# bus.net
KiCad netlist of a schematic drawn in Altium Designer
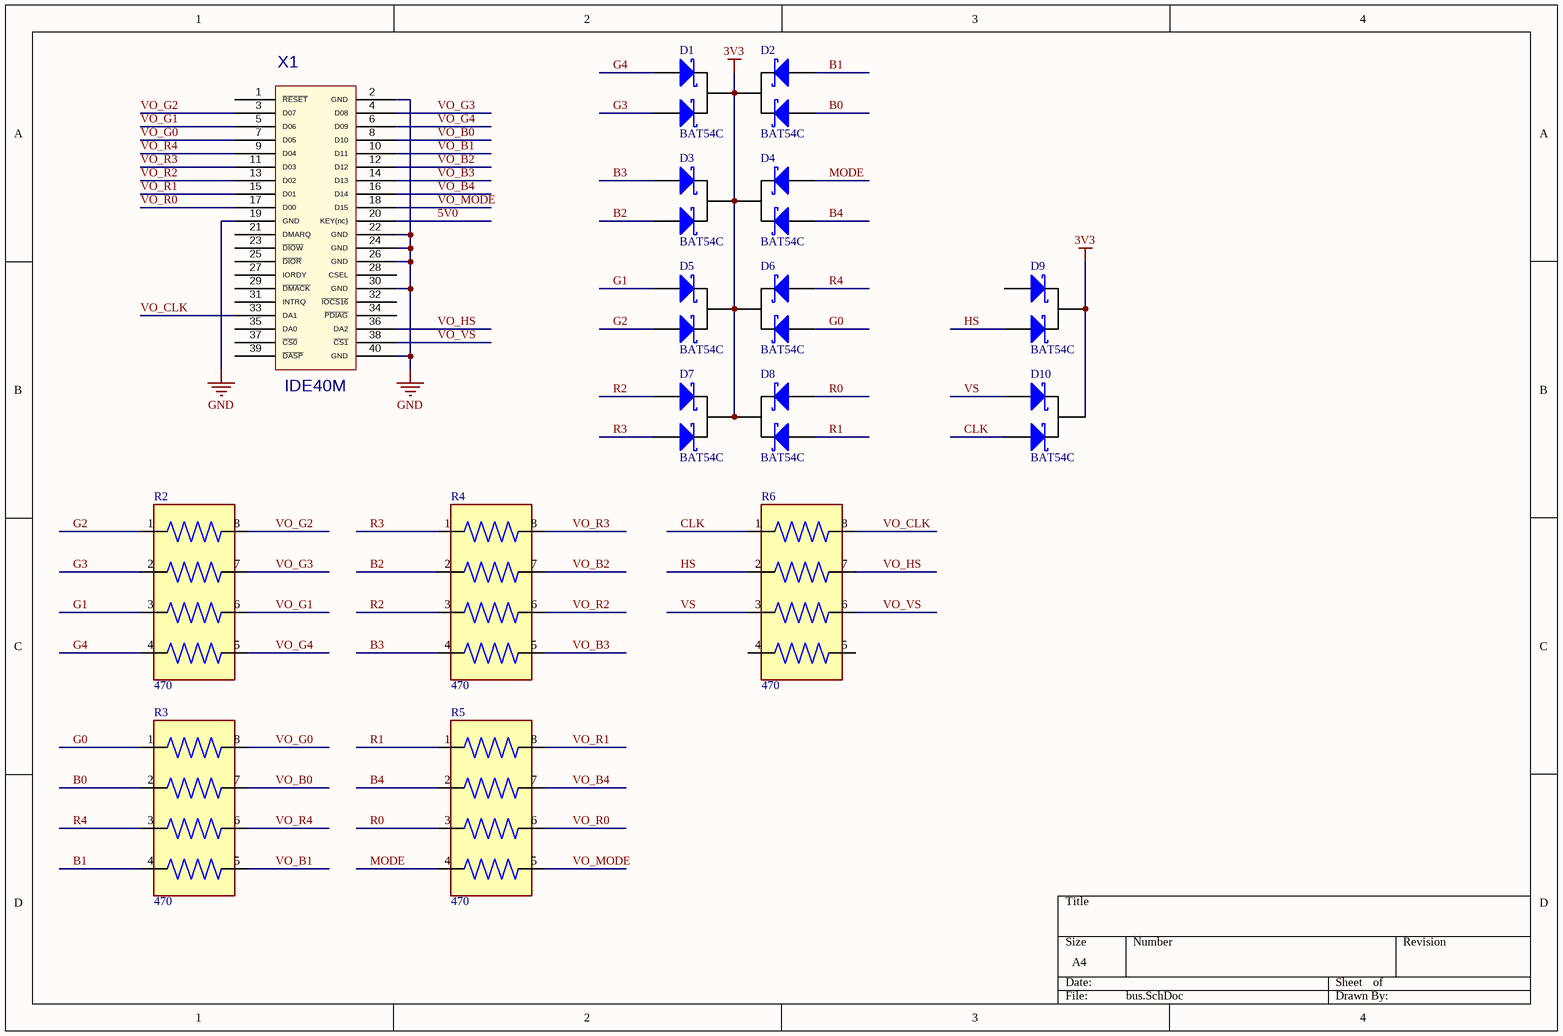
[diagram p0: bus.SchDoc]

(export (version "E")
  (design (tool "Eeschema 10.0.6"))
  (components
    (comp (ref "D1") (value "BAT54C") (footprint "SOT-23") (libsource (lib "Schlib") (part "BAT54C")))
    (comp (ref "D2") (value "BAT54C") (footprint "SOT-23") (libsource (lib "Schlib") (part "BAT54C")))
    (comp (ref "D3") (value "BAT54C") (footprint "SOT-23") (libsource (lib "Schlib") (part "BAT54C")))
    (comp (ref "D4") (value "BAT54C") (footprint "SOT-23") (libsource (lib "Schlib") (part "BAT54C")))
    (comp (ref "D5") (value "BAT54C") (footprint "SOT-23") (libsource (lib "Schlib") (part "BAT54C")))
    (comp (ref "D6") (value "BAT54C") (footprint "SOT-23") (libsource (lib "Schlib") (part "BAT54C")))
    (comp (ref "D7") (value "BAT54C") (footprint "SOT-23") (libsource (lib "Schlib") (part "BAT54C")))
    (comp (ref "D8") (value "BAT54C") (footprint "SOT-23") (libsource (lib "Schlib") (part "BAT54C")))
    (comp (ref "D9") (value "BAT54C") (footprint "SOT-23") (libsource (lib "Schlib") (part "BAT54C")))
    (comp (ref "D10") (value "BAT54C") (footprint "SOT-23") (libsource (lib "Schlib") (part "BAT54C")))
    (comp (ref "R2")
      (value "470")
      (footprint "RESCAV50P200X100X55-8N")
      (fields (field (name "MP") "CAT10-101J4LF"))
      (libsource (lib "Schlib") (part "CAT10-***4LF"))
    )
    (comp (ref "R3")
      (value "470")
      (footprint "RESCAV50P200X100X55-8N")
      (fields (field (name "MP") "CAT10-101J4LF"))
      (libsource (lib "Schlib") (part "CAT10-***4LF"))
    )
    (comp (ref "R4")
      (value "470")
      (footprint "RESCAV50P200X100X55-8N")
      (fields (field (name "MP") "CAT10-101J4LF"))
      (libsource (lib "Schlib") (part "CAT10-***4LF"))
    )
    (comp (ref "R5")
      (value "470")
      (footprint "RESCAV50P200X100X55-8N")
      (fields (field (name "MP") "CAT10-101J4LF"))
      (libsource (lib "Schlib") (part "CAT10-***4LF"))
    )
    (comp (ref "R6")
      (value "470")
      (footprint "RESCAV50P200X100X55-8N")
      (fields (field (name "MP") "CAT10-101J4LF"))
      (libsource (lib "Schlib") (part "CAT10-***4LF"))
    )
    (comp (ref "X1") (value "IDE40M") (footprint "IDE40M") (libsource (lib "Schlib") (part "IDE40M")))
  )
  (nets
    (net (code "1") (name "/5V0") (class "Default")
      (node (ref "X1") (pin "20") (pinfunction "KEY(nc)_20") (pintype "passive"))
    )
    (net (code "2") (name "/B0") (class "Default")
      (node (ref "D2") (pin "2") (pinfunction "A_2") (pintype "passive"))
      (node (ref "R3") (pin "2") (pinfunction "2_2") (pintype "passive"))
    )
    (net (code "3") (name "/B1") (class "Default")
      (node (ref "D2") (pin "1") (pinfunction "A_1") (pintype "passive"))
      (node (ref "R3") (pin "4") (pinfunction "4_4") (pintype "passive"))
    )
    (net (code "4") (name "/B2") (class "Default")
      (node (ref "D3") (pin "2") (pinfunction "A_2") (pintype "passive"))
      (node (ref "R4") (pin "2") (pinfunction "2_2") (pintype "passive"))
    )
    (net (code "5") (name "/B3") (class "Default")
      (node (ref "D3") (pin "1") (pinfunction "A_1") (pintype "passive"))
      (node (ref "R4") (pin "4") (pinfunction "4_4") (pintype "passive"))
    )
    (net (code "6") (name "/B4") (class "Default")
      (node (ref "D4") (pin "2") (pinfunction "A_2") (pintype "passive"))
      (node (ref "R5") (pin "2") (pinfunction "2_2") (pintype "passive"))
    )
    (net (code "7") (name "/CLK") (class "Default")
      (node (ref "D10") (pin "2") (pinfunction "A_2") (pintype "passive"))
      (node (ref "R6") (pin "1") (pinfunction "1_1") (pintype "passive"))
    )
    (net (code "8") (name "/G0") (class "Default")
      (node (ref "D6") (pin "2") (pinfunction "A_2") (pintype "passive"))
      (node (ref "R3") (pin "1") (pinfunction "1_1") (pintype "passive"))
    )
    (net (code "9") (name "/G1") (class "Default")
      (node (ref "D5") (pin "1") (pinfunction "A_1") (pintype "passive"))
      (node (ref "R2") (pin "3") (pinfunction "3_3") (pintype "passive"))
    )
    (net (code "10") (name "/G2") (class "Default")
      (node (ref "D5") (pin "2") (pinfunction "A_2") (pintype "passive"))
      (node (ref "R2") (pin "1") (pinfunction "1_1") (pintype "passive"))
    )
    (net (code "11") (name "/G3") (class "Default")
      (node (ref "D1") (pin "2") (pinfunction "A_2") (pintype "passive"))
      (node (ref "R2") (pin "2") (pinfunction "2_2") (pintype "passive"))
    )
    (net (code "12") (name "/G4") (class "Default")
      (node (ref "D1") (pin "1") (pinfunction "A_1") (pintype "passive"))
      (node (ref "R2") (pin "4") (pinfunction "4_4") (pintype "passive"))
    )
    (net (code "13") (name "/HS") (class "Default")
      (node (ref "D9") (pin "2") (pinfunction "A_2") (pintype "passive"))
      (node (ref "R6") (pin "2") (pinfunction "2_2") (pintype "passive"))
    )
    (net (code "14") (name "/MODE") (class "Default")
      (node (ref "D4") (pin "1") (pinfunction "A_1") (pintype "passive"))
      (node (ref "R5") (pin "4") (pinfunction "4_4") (pintype "passive"))
    )
    (net (code "15") (name "/R0") (class "Default")
      (node (ref "D8") (pin "1") (pinfunction "A_1") (pintype "passive"))
      (node (ref "R5") (pin "3") (pinfunction "3_3") (pintype "passive"))
    )
    (net (code "16") (name "/R1") (class "Default")
      (node (ref "D8") (pin "2") (pinfunction "A_2") (pintype "passive"))
      (node (ref "R5") (pin "1") (pinfunction "1_1") (pintype "passive"))
    )
    (net (code "17") (name "/R2") (class "Default")
      (node (ref "D7") (pin "1") (pinfunction "A_1") (pintype "passive"))
      (node (ref "R4") (pin "3") (pinfunction "3_3") (pintype "passive"))
    )
    (net (code "18") (name "/R3") (class "Default")
      (node (ref "D7") (pin "2") (pinfunction "A_2") (pintype "passive"))
      (node (ref "R4") (pin "1") (pinfunction "1_1") (pintype "passive"))
    )
    (net (code "19") (name "/R4") (class "Default")
      (node (ref "D6") (pin "1") (pinfunction "A_1") (pintype "passive"))
      (node (ref "R3") (pin "3") (pinfunction "3_3") (pintype "passive"))
    )
    (net (code "20") (name "/VO_B0") (class "Default")
      (node (ref "R3") (pin "7") (pinfunction "7_7") (pintype "passive"))
      (node (ref "X1") (pin "8") (pinfunction "D10_8") (pintype "passive"))
    )
    (net (code "21") (name "/VO_B1") (class "Default")
      (node (ref "R3") (pin "5") (pinfunction "5_5") (pintype "passive"))
      (node (ref "X1") (pin "10") (pinfunction "D11_10") (pintype "passive"))
    )
    (net (code "22") (name "/VO_B2") (class "Default")
      (node (ref "R4") (pin "7") (pinfunction "7_7") (pintype "passive"))
      (node (ref "X1") (pin "12") (pinfunction "D12_12") (pintype "passive"))
    )
    (net (code "23") (name "/VO_B3") (class "Default")
      (node (ref "R4") (pin "5") (pinfunction "5_5") (pintype "passive"))
      (node (ref "X1") (pin "14") (pinfunction "D13_14") (pintype "passive"))
    )
    (net (code "24") (name "/VO_B4") (class "Default")
      (node (ref "R5") (pin "7") (pinfunction "7_7") (pintype "passive"))
      (node (ref "X1") (pin "16") (pinfunction "D14_16") (pintype "passive"))
    )
    (net (code "25") (name "/VO_CLK") (class "Default")
      (node (ref "R6") (pin "8") (pinfunction "8_8") (pintype "passive"))
      (node (ref "X1") (pin "33") (pinfunction "DA1_33") (pintype "passive"))
    )
    (net (code "26") (name "/VO_G0") (class "Default")
      (node (ref "R3") (pin "8") (pinfunction "8_8") (pintype "passive"))
      (node (ref "X1") (pin "7") (pinfunction "D05_7") (pintype "passive"))
    )
    (net (code "27") (name "/VO_G1") (class "Default")
      (node (ref "R2") (pin "6") (pinfunction "6_6") (pintype "passive"))
      (node (ref "X1") (pin "5") (pinfunction "D06_5") (pintype "passive"))
    )
    (net (code "28") (name "/VO_G2") (class "Default")
      (node (ref "R2") (pin "8") (pinfunction "8_8") (pintype "passive"))
      (node (ref "X1") (pin "3") (pinfunction "D07_3") (pintype "passive"))
    )
    (net (code "29") (name "/VO_G3") (class "Default")
      (node (ref "R2") (pin "7") (pinfunction "7_7") (pintype "passive"))
      (node (ref "X1") (pin "4") (pinfunction "D08_4") (pintype "passive"))
    )
    (net (code "30") (name "/VO_G4") (class "Default")
      (node (ref "R2") (pin "5") (pinfunction "5_5") (pintype "passive"))
      (node (ref "X1") (pin "6") (pinfunction "D09_6") (pintype "passive"))
    )
    (net (code "31") (name "/VO_HS") (class "Default")
      (node (ref "R6") (pin "7") (pinfunction "7_7") (pintype "passive"))
      (node (ref "X1") (pin "36") (pinfunction "DA2_36") (pintype "passive"))
    )
    (net (code "32") (name "/VO_MODE") (class "Default")
      (node (ref "R5") (pin "5") (pinfunction "5_5") (pintype "passive"))
      (node (ref "X1") (pin "18") (pinfunction "D15_18") (pintype "passive"))
    )
    (net (code "33") (name "/VO_R0") (class "Default")
      (node (ref "R5") (pin "6") (pinfunction "6_6") (pintype "passive"))
      (node (ref "X1") (pin "17") (pinfunction "D00_17") (pintype "passive"))
    )
    (net (code "34") (name "/VO_R1") (class "Default")
      (node (ref "R5") (pin "8") (pinfunction "8_8") (pintype "passive"))
      (node (ref "X1") (pin "15") (pinfunction "D01_15") (pintype "passive"))
    )
    (net (code "35") (name "/VO_R2") (class "Default")
      (node (ref "R4") (pin "6") (pinfunction "6_6") (pintype "passive"))
      (node (ref "X1") (pin "13") (pinfunction "D02_13") (pintype "passive"))
    )
    (net (code "36") (name "/VO_R3") (class "Default")
      (node (ref "R4") (pin "8") (pinfunction "8_8") (pintype "passive"))
      (node (ref "X1") (pin "11") (pinfunction "D03_11") (pintype "passive"))
    )
    (net (code "37") (name "/VO_R4") (class "Default")
      (node (ref "R3") (pin "6") (pinfunction "6_6") (pintype "passive"))
      (node (ref "X1") (pin "9") (pinfunction "D04_9") (pintype "passive"))
    )
    (net (code "38") (name "/VO_VS") (class "Default")
      (node (ref "R6") (pin "6") (pinfunction "6_6") (pintype "passive"))
      (node (ref "X1") (pin "38") (pinfunction "~{CS1}_38") (pintype "passive"))
    )
    (net (code "39") (name "/VS") (class "Default")
      (node (ref "D10") (pin "1") (pinfunction "A_1") (pintype "passive"))
      (node (ref "R6") (pin "3") (pinfunction "3_3") (pintype "passive"))
    )
    (net (code "40") (name "3V3") (class "Default")
      (node (ref "D1") (pin "3") (pinfunction "C_3") (pintype "passive"))
      (node (ref "D10") (pin "3") (pinfunction "C_3") (pintype "passive"))
      (node (ref "D2") (pin "3") (pinfunction "C_3") (pintype "passive"))
      (node (ref "D3") (pin "3") (pinfunction "C_3") (pintype "passive"))
      (node (ref "D4") (pin "3") (pinfunction "C_3") (pintype "passive"))
      (node (ref "D5") (pin "3") (pinfunction "C_3") (pintype "passive"))
      (node (ref "D6") (pin "3") (pinfunction "C_3") (pintype "passive"))
      (node (ref "D7") (pin "3") (pinfunction "C_3") (pintype "passive"))
      (node (ref "D8") (pin "3") (pinfunction "C_3") (pintype "passive"))
      (node (ref "D9") (pin "3") (pinfunction "C_3") (pintype "passive"))
    )
    (net (code "41") (name "GND") (class "Default")
      (node (ref "X1") (pin "19") (pinfunction "GND_19") (pintype "passive"))
      (node (ref "X1") (pin "2") (pinfunction "GND_2") (pintype "passive"))
      (node (ref "X1") (pin "22") (pinfunction "GND_22") (pintype "passive"))
      (node (ref "X1") (pin "24") (pinfunction "GND_24") (pintype "passive"))
      (node (ref "X1") (pin "26") (pinfunction "GND_26") (pintype "passive"))
      (node (ref "X1") (pin "30") (pinfunction "GND_30") (pintype "passive"))
      (node (ref "X1") (pin "40") (pinfunction "GND_40") (pintype "passive"))
    )
    (net (code "42") (name "unconnected-(D9-A-Pad1)") (class "Default")
      (node (ref "D9") (pin "1") (pinfunction "A_1") (pintype "passive"))
    )
    (net (code "43") (name "unconnected-(R6-Pad4)") (class "Default")
      (node (ref "R6") (pin "4") (pinfunction "4_4") (pintype "passive"))
    )
    (net (code "44") (name "unconnected-(R6-Pad5)") (class "Default")
      (node (ref "R6") (pin "5") (pinfunction "5_5") (pintype "passive"))
    )
    (net (code "45") (name "unconnected-(X1-CSEL-Pad28)") (class "Default")
      (node (ref "X1") (pin "28") (pinfunction "CSEL_28") (pintype "passive"))
    )
    (net (code "46") (name "unconnected-(X1-DA0-Pad35)") (class "Default")
      (node (ref "X1") (pin "35") (pinfunction "DA0_35") (pintype "passive"))
    )
    (net (code "47") (name "unconnected-(X1-DMARQ-Pad21)") (class "Default")
      (node (ref "X1") (pin "21") (pinfunction "DMARQ_21") (pintype "passive"))
    )
    (net (code "48") (name "unconnected-(X1-INTRQ-Pad31)") (class "Default")
      (node (ref "X1") (pin "31") (pinfunction "INTRQ_31") (pintype "passive"))
    )
    (net (code "49") (name "unconnected-(X1-IORDY-Pad27)") (class "Default")
      (node (ref "X1") (pin "27") (pinfunction "IORDY_27") (pintype "passive"))
    )
    (net (code "50") (name "unconnected-(X1-~{CS0}-Pad37)") (class "Default")
      (node (ref "X1") (pin "37") (pinfunction "~{CS0}_37") (pintype "passive"))
    )
    (net (code "51") (name "unconnected-(X1-~{DASP}-Pad39)") (class "Default")
      (node (ref "X1") (pin "39") (pinfunction "~{DASP}_39") (pintype "passive"))
    )
    (net (code "52") (name "unconnected-(X1-~{DIOR}-Pad25)") (class "Default")
      (node (ref "X1") (pin "25") (pinfunction "~{DIOR}_25") (pintype "passive"))
    )
    (net (code "53") (name "unconnected-(X1-~{DIOW}-Pad23)") (class "Default")
      (node (ref "X1") (pin "23") (pinfunction "~{DIOW}_23") (pintype "passive"))
    )
    (net (code "54") (name "unconnected-(X1-~{DMACK}-Pad29)") (class "Default")
      (node (ref "X1") (pin "29") (pinfunction "~{DMACK}_29") (pintype "passive"))
    )
    (net (code "55") (name "unconnected-(X1-~{IOCS16}-Pad32)") (class "Default")
      (node (ref "X1") (pin "32") (pinfunction "~{IOCS16}_32") (pintype "passive"))
    )
    (net (code "56") (name "unconnected-(X1-~{PDIAG}-Pad34)") (class "Default")
      (node (ref "X1") (pin "34") (pinfunction "~{PDIAG}_34") (pintype "passive"))
    )
    (net (code "57") (name "unconnected-(X1-~{RESET}-Pad1)") (class "Default")
      (node (ref "X1") (pin "1") (pinfunction "~{RESET}_1") (pintype "passive"))
    )
  )
)
